# power_supply.net
KiCad netlist of a schematic drawn in Altium Designer
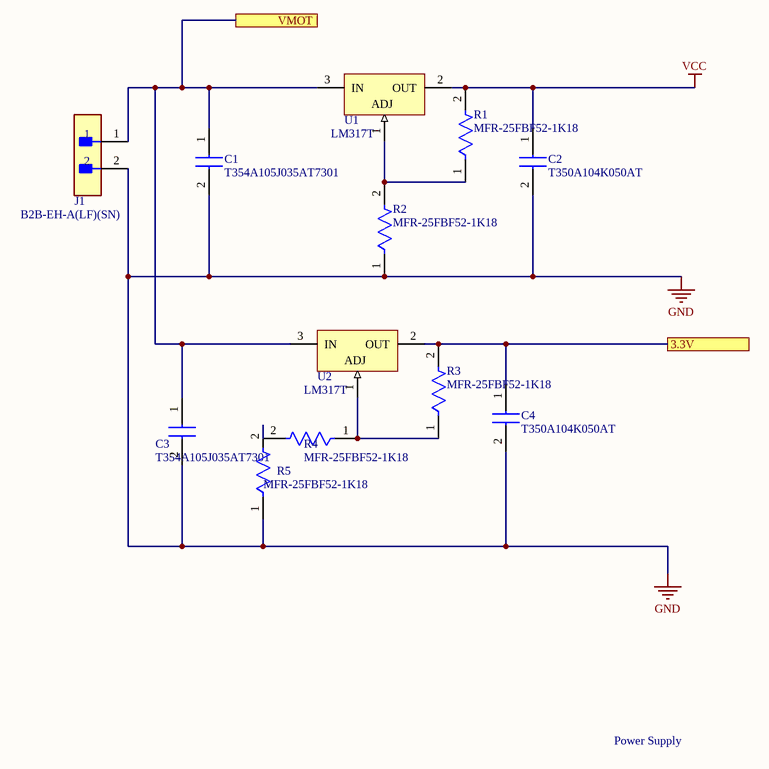
[diagram p0: power supply.SchDoc]

(export (version "E")
  (design (tool "Eeschema 10.0.6"))
  (components
    (comp (ref "C1")
      (value "T354A105J035AT7301")
      (footprint "SamacSys:T354A105J035AT7301")
      (description "Capacitor")
      (fields (field (name "MOUSER PART NUMBER") "80-T354A105J35AT-TR"))
      (libsource (lib "*") (part "T354A105J035AT7301"))
    )
    (comp (ref "C2")
      (value "T350A104K050AT")
      (footprint "SamacSys:T350A104K050AT")
      (description "Capacitor")
      (fields (field (name "MOUSER PART NUMBER") "80-T350A104K50AT"))
      (libsource (lib "*") (part "T350A104K050AT"))
    )
    (comp (ref "C3")
      (value "T354A105J035AT7301")
      (footprint "SamacSys:T354A105J035AT7301")
      (description "Capacitor")
      (fields (field (name "MOUSER PART NUMBER") "80-T354A105J35AT-TR"))
      (libsource (lib "*") (part "T354A105J035AT7301"))
    )
    (comp (ref "C4")
      (value "T350A104K050AT")
      (footprint "SamacSys:T350A104K050AT")
      (description "Capacitor")
      (fields (field (name "MOUSER PART NUMBER") "80-T350A104K50AT"))
      (libsource (lib "*") (part "T350A104K050AT"))
    )
    (comp (ref "J1")
      (value "B2B-EH-A(LF)(SN)")
      (footprint "FP-B2B-EH-A_LF_SN-MFG")
      (description "CONN HEADER VERT 2POS 2.5MM")
      (libsource (lib "Altium Content Vault") (part "3bc925449376181038e59eaffc5286c"))
    )
    (comp (ref "R1")
      (value "MFR-25FBF52-1K18")
      (footprint "FP-MFR-25-MFG")
      (description "RES 1.18K OHM 1/4W 1% AXIAL")
      (fields (field (name "MANUFACTURER") "Yageo") (field (name "TOLERANCE") "1%"))
      (libsource (lib "Altium Content Vault") (part "1029c3af85768c4190bb7ad29bc67b5"))
    )
    (comp (ref "R2")
      (value "MFR-25FBF52-1K18")
      (footprint "FP-MFR-25-MFG")
      (description "RES 1.18K OHM 1/4W 1% AXIAL")
      (fields (field (name "MANUFACTURER") "Yageo") (field (name "TOLERANCE") "1%"))
      (libsource (lib "Altium Content Vault") (part "1029c3af85768c4190bb7ad29bc67b5"))
    )
    (comp (ref "R3")
      (value "MFR-25FBF52-1K18")
      (footprint "FP-MFR-25-MFG")
      (description "RES 1.18K OHM 1/4W 1% AXIAL")
      (fields (field (name "MANUFACTURER") "Yageo") (field (name "TOLERANCE") "1%"))
      (libsource (lib "Altium Content Vault") (part "1029c3af85768c4190bb7ad29bc67b5"))
    )
    (comp (ref "R4")
      (value "MFR-25FBF52-1K18")
      (footprint "FP-MFR-25-MFG")
      (description "RES 1.18K OHM 1/4W 1% AXIAL")
      (fields (field (name "MANUFACTURER") "Yageo") (field (name "TOLERANCE") "1%"))
      (libsource (lib "Altium Content Vault") (part "1029c3af85768c4190bb7ad29bc67b5"))
    )
    (comp (ref "R5")
      (value "MFR-25FBF52-1K18")
      (footprint "FP-MFR-25-MFG")
      (description "RES 1.18K OHM 1/4W 1% AXIAL")
      (fields (field (name "MANUFACTURER") "Yageo") (field (name "TOLERANCE") "1%"))
      (libsource (lib "Altium Content Vault") (part "1029c3af85768c4190bb7ad29bc67b5"))
    )
    (comp (ref "U1")
      (value "LM317T")
      (footprint "NDE0003A")
      (description "3-Terminal Adjustable Regulator, 3-pin TO-220")
      (fields (field (name "MANUFACTURER") "Texas Instruments"))
      (libsource (lib "Altium Content Vault") (part "PM-REG-LM1086ADJ-SIL3"))
    )
    (comp (ref "U2")
      (value "LM317T")
      (footprint "NDE0003A")
      (description "3-Terminal Adjustable Regulator, 3-pin TO-220")
      (fields (field (name "MANUFACTURER") "Texas Instruments"))
      (libsource (lib "Altium Content Vault") (part "PM-REG-LM1086ADJ-SIL3"))
    )
  )
  (nets
    (net (code "1") (name "/3.3V") (class "Default")
      (node (ref "C4") (pin "1") (pinfunction "1_1") (pintype "passive"))
      (node (ref "R3") (pin "2") (pinfunction "2_2") (pintype "passive"))
      (node (ref "U2") (pin "2") (pinfunction "OUT_2") (pintype "power_in"))
    )
    (net (code "2") (name "/VMOT") (class "Default")
      (node (ref "C1") (pin "1") (pinfunction "+_1") (pintype "passive"))
      (node (ref "C3") (pin "1") (pinfunction "+_1") (pintype "passive"))
      (node (ref "J1") (pin "1") (pinfunction "1_1") (pintype "passive"))
      (node (ref "U1") (pin "3") (pinfunction "IN_3") (pintype "power_in"))
      (node (ref "U2") (pin "3") (pinfunction "IN_3") (pintype "power_in"))
    )
    (net (code "3") (name "GND") (class "Default")
      (node (ref "C1") (pin "2") (pinfunction "-_2") (pintype "passive"))
      (node (ref "C2") (pin "2") (pinfunction "2_2") (pintype "passive"))
      (node (ref "C3") (pin "2") (pinfunction "-_2") (pintype "passive"))
      (node (ref "C4") (pin "2") (pinfunction "2_2") (pintype "passive"))
      (node (ref "J1") (pin "2") (pinfunction "2_2") (pintype "passive"))
      (node (ref "R2") (pin "1") (pinfunction "1_1") (pintype "passive"))
      (node (ref "R5") (pin "1") (pinfunction "1_1") (pintype "passive"))
    )
    (net (code "4") (name "Net-(R4-Pad2)") (class "Default")
      (node (ref "R4") (pin "2") (pinfunction "2_2") (pintype "passive"))
      (node (ref "R5") (pin "2") (pinfunction "2_2") (pintype "passive"))
    )
    (net (code "5") (name "Net-(U1-ADJ)") (class "Default")
      (node (ref "R1") (pin "1") (pinfunction "1_1") (pintype "passive"))
      (node (ref "R2") (pin "2") (pinfunction "2_2") (pintype "passive"))
      (node (ref "U1") (pin "1") (pinfunction "ADJ_1") (pintype "input"))
    )
    (net (code "6") (name "Net-(U2-ADJ)") (class "Default")
      (node (ref "R3") (pin "1") (pinfunction "1_1") (pintype "passive"))
      (node (ref "R4") (pin "1") (pinfunction "1_1") (pintype "passive"))
      (node (ref "U2") (pin "1") (pinfunction "ADJ_1") (pintype "input"))
    )
    (net (code "7") (name "VCC") (class "Default")
      (node (ref "C2") (pin "1") (pinfunction "1_1") (pintype "passive"))
      (node (ref "R1") (pin "2") (pinfunction "2_2") (pintype "passive"))
      (node (ref "U1") (pin "2") (pinfunction "OUT_2") (pintype "power_in"))
    )
  )
)
